# FPGA.net
KiCad netlist of a schematic drawn in Altium Designer
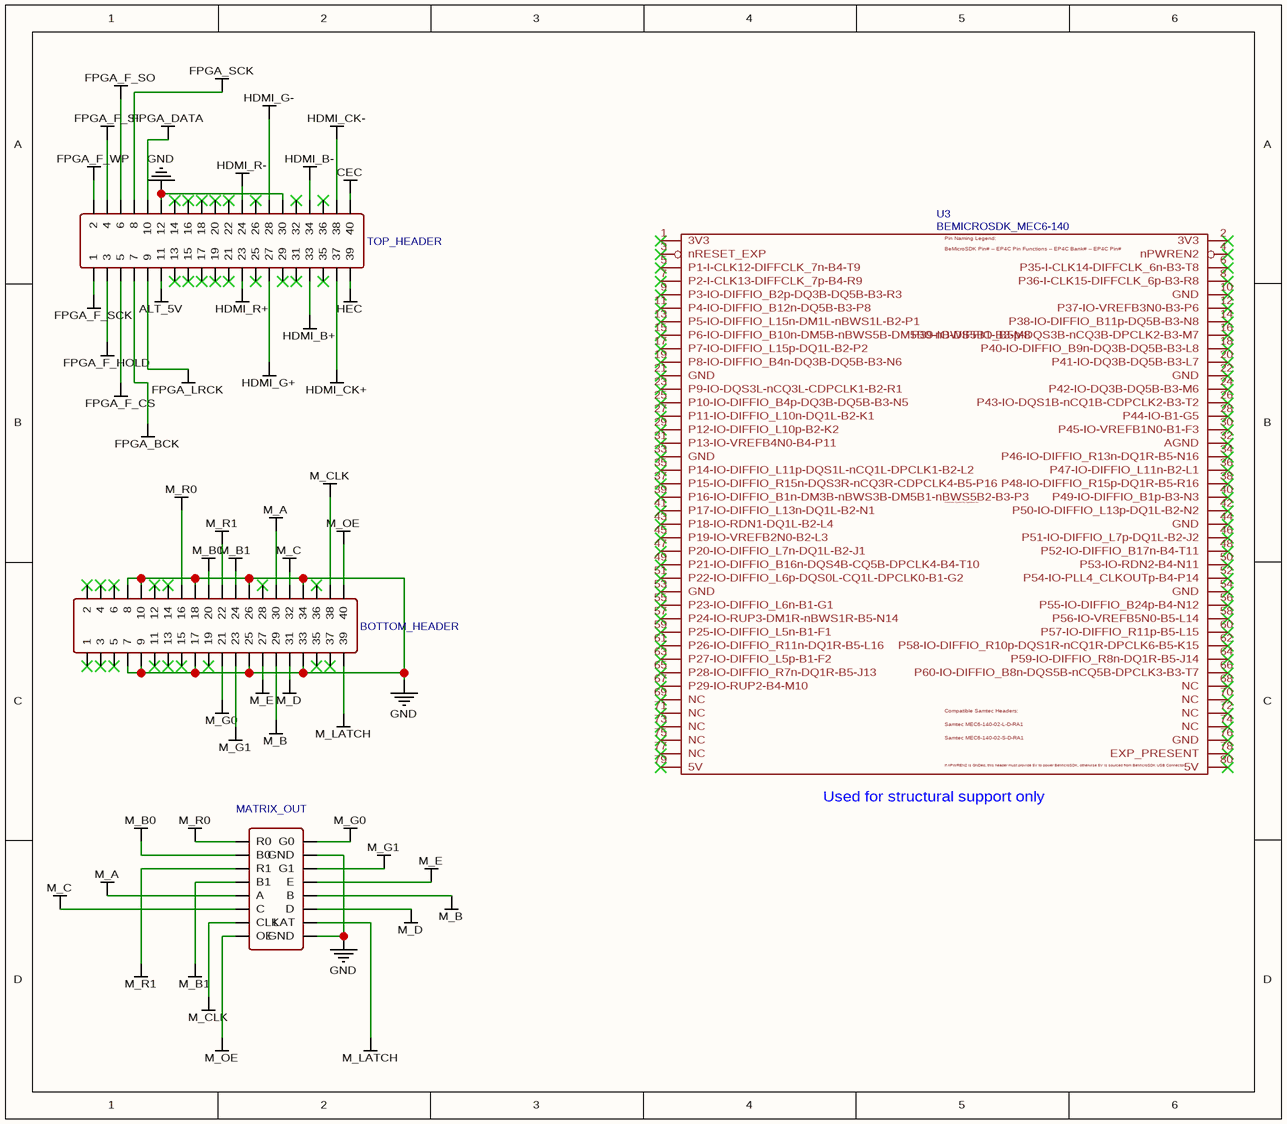
[diagram p0: FPGA.schdoc]

(export (version "E")
  (design (tool "Eeschema 10.0.6"))
  (components
    (comp (ref "BOTTOM_HEADER")
      (value "Header-Male-2.54_2x20")
      (fields (field (name "BOM_SUPPLIER PART") "C50980"))
      (libsource (lib "altium-import") (part "root_1_Header-Male-2.54_2x20_"))
    )
    (comp (ref "MATRIX_OUT")
      (value "MATRIX_OUT")
      (fields
        (field (name "BOM_MANUFACTURER PART") "Double row straight 2*8Headers  Pins 2.54mm")
        (field (name "BOM_SUPPLIER PART") "C68234")
      )
      (libsource (lib "altium-import") (part "root_0_MATRIX_OUT_"))
    )
    (comp (ref "TOP_HEADER")
      (value "Header-Mal0")
      (fields
        (field (name "BOM_MANUFACTURER PART") "Header-Male-2.54_2x20")
        (field (name "BOM_SUPPLIER PART") "C50980")
      )
      (libsource (lib "altium-import") (part "root_1_Header-Mal0_"))
    )
    (comp (ref "U3")
      (value "BEMICROSDK_MEC6-140")
      (fields (field (name "BOM_MANUFACTURER PART") "?"))
      (libsource (lib "altium-import") (part "root_0_BEMICROSDK_MEC6-140_"))
    )
  )
  (nets
    (net (code "1") (name "ALT_5V") (class "Default")
      (node (ref "TOP_HEADER") (pin "11") (pinfunction "11_11") (pintype "passive"))
    )
    (net (code "2") (name "CEC") (class "Default")
      (node (ref "TOP_HEADER") (pin "40") (pinfunction "40_40") (pintype "passive"))
    )
    (net (code "3") (name "FPGA_BCK") (class "Default")
      (node (ref "TOP_HEADER") (pin "7") (pinfunction "7_7") (pintype "passive"))
    )
    (net (code "4") (name "FPGA_DATA") (class "Default")
      (node (ref "TOP_HEADER") (pin "10") (pinfunction "10_10") (pintype "passive"))
    )
    (net (code "5") (name "FPGA_F_CS") (class "Default")
      (node (ref "TOP_HEADER") (pin "5") (pinfunction "5_5") (pintype "passive"))
    )
    (net (code "6") (name "FPGA_F_HOLD") (class "Default")
      (node (ref "TOP_HEADER") (pin "3") (pinfunction "3_3") (pintype "passive"))
    )
    (net (code "7") (name "FPGA_F_SCK") (class "Default")
      (node (ref "TOP_HEADER") (pin "1") (pinfunction "1_1") (pintype "passive"))
    )
    (net (code "8") (name "FPGA_F_SI") (class "Default")
      (node (ref "TOP_HEADER") (pin "4") (pinfunction "4_4") (pintype "passive"))
    )
    (net (code "9") (name "FPGA_F_SO") (class "Default")
      (node (ref "TOP_HEADER") (pin "6") (pinfunction "6_6") (pintype "passive"))
    )
    (net (code "10") (name "FPGA_F_WP") (class "Default")
      (node (ref "TOP_HEADER") (pin "2") (pinfunction "2_2") (pintype "passive"))
    )
    (net (code "11") (name "FPGA_LRCK") (class "Default")
      (node (ref "TOP_HEADER") (pin "9") (pinfunction "9_9") (pintype "passive"))
    )
    (net (code "12") (name "FPGA_SCK") (class "Default")
      (node (ref "TOP_HEADER") (pin "8") (pinfunction "8_8") (pintype "passive"))
    )
    (net (code "13") (name "GND") (class "Default")
      (node (ref "BOTTOM_HEADER") (pin "10") (pinfunction "10_10") (pintype "passive"))
      (node (ref "BOTTOM_HEADER") (pin "17") (pinfunction "17_17") (pintype "passive"))
      (node (ref "BOTTOM_HEADER") (pin "18") (pinfunction "18_18") (pintype "passive"))
      (node (ref "BOTTOM_HEADER") (pin "25") (pinfunction "25_25") (pintype "passive"))
      (node (ref "BOTTOM_HEADER") (pin "26") (pinfunction "26_26") (pintype "passive"))
      (node (ref "BOTTOM_HEADER") (pin "33") (pinfunction "33_33") (pintype "passive"))
      (node (ref "BOTTOM_HEADER") (pin "34") (pinfunction "34_34") (pintype "passive"))
      (node (ref "BOTTOM_HEADER") (pin "7") (pinfunction "7_7") (pintype "passive"))
      (node (ref "BOTTOM_HEADER") (pin "8") (pinfunction "8_8") (pintype "passive"))
      (node (ref "BOTTOM_HEADER") (pin "9") (pinfunction "9_9") (pintype "passive"))
      (node (ref "MATRIX_OUT") (pin "16") (pinfunction "GND_16") (pintype "passive"))
      (node (ref "MATRIX_OUT") (pin "4") (pinfunction "GND_4") (pintype "passive"))
      (node (ref "TOP_HEADER") (pin "12") (pinfunction "12_12") (pintype "passive"))
      (node (ref "TOP_HEADER") (pin "30") (pinfunction "30_30") (pintype "passive"))
    )
    (net (code "14") (name "HDMI_B+") (class "Default")
      (node (ref "TOP_HEADER") (pin "33") (pinfunction "33_33") (pintype "passive"))
    )
    (net (code "15") (name "HDMI_B-") (class "Default")
      (node (ref "TOP_HEADER") (pin "34") (pinfunction "34_34") (pintype "passive"))
    )
    (net (code "16") (name "HDMI_CK+") (class "Default")
      (node (ref "TOP_HEADER") (pin "37") (pinfunction "37_37") (pintype "passive"))
    )
    (net (code "17") (name "HDMI_CK-") (class "Default")
      (node (ref "TOP_HEADER") (pin "38") (pinfunction "38_38") (pintype "passive"))
    )
    (net (code "18") (name "HDMI_G+") (class "Default")
      (node (ref "TOP_HEADER") (pin "27") (pinfunction "27_27") (pintype "passive"))
    )
    (net (code "19") (name "HDMI_G-") (class "Default")
      (node (ref "TOP_HEADER") (pin "28") (pinfunction "28_28") (pintype "passive"))
    )
    (net (code "20") (name "HDMI_R+") (class "Default")
      (node (ref "TOP_HEADER") (pin "23") (pinfunction "23_23") (pintype "passive"))
    )
    (net (code "21") (name "HDMI_R-") (class "Default")
      (node (ref "TOP_HEADER") (pin "24") (pinfunction "24_24") (pintype "passive"))
    )
    (net (code "22") (name "HEC") (class "Default")
      (node (ref "TOP_HEADER") (pin "39") (pinfunction "39_39") (pintype "passive"))
    )
    (net (code "23") (name "M_A") (class "Default")
      (node (ref "BOTTOM_HEADER") (pin "30") (pinfunction "30_30") (pintype "passive"))
      (node (ref "MATRIX_OUT") (pin "9") (pinfunction "A_9") (pintype "passive"))
    )
    (net (code "24") (name "M_B") (class "Default")
      (node (ref "BOTTOM_HEADER") (pin "29") (pinfunction "29_29") (pintype "passive"))
      (node (ref "MATRIX_OUT") (pin "10") (pinfunction "B_10") (pintype "passive"))
    )
    (net (code "25") (name "M_B0") (class "Default")
      (node (ref "BOTTOM_HEADER") (pin "20") (pinfunction "20_20") (pintype "passive"))
      (node (ref "MATRIX_OUT") (pin "3") (pinfunction "B0_3") (pintype "passive"))
    )
    (net (code "26") (name "M_B1") (class "Default")
      (node (ref "BOTTOM_HEADER") (pin "24") (pinfunction "24_24") (pintype "passive"))
      (node (ref "MATRIX_OUT") (pin "7") (pinfunction "B1_7") (pintype "passive"))
    )
    (net (code "27") (name "M_C") (class "Default")
      (node (ref "BOTTOM_HEADER") (pin "32") (pinfunction "32_32") (pintype "passive"))
      (node (ref "MATRIX_OUT") (pin "11") (pinfunction "C_11") (pintype "passive"))
    )
    (net (code "28") (name "M_CLK") (class "Default")
      (node (ref "BOTTOM_HEADER") (pin "38") (pinfunction "38_38") (pintype "passive"))
      (node (ref "MATRIX_OUT") (pin "13") (pinfunction "CLK_13") (pintype "passive"))
    )
    (net (code "29") (name "M_D") (class "Default")
      (node (ref "BOTTOM_HEADER") (pin "31") (pinfunction "31_31") (pintype "passive"))
      (node (ref "MATRIX_OUT") (pin "12") (pinfunction "D_12") (pintype "passive"))
    )
    (net (code "30") (name "M_E") (class "Default")
      (node (ref "BOTTOM_HEADER") (pin "27") (pinfunction "27_27") (pintype "passive"))
      (node (ref "MATRIX_OUT") (pin "8") (pinfunction "E_8") (pintype "passive"))
    )
    (net (code "31") (name "M_G0") (class "Default")
      (node (ref "BOTTOM_HEADER") (pin "21") (pinfunction "21_21") (pintype "passive"))
      (node (ref "MATRIX_OUT") (pin "2") (pinfunction "G0_2") (pintype "passive"))
    )
    (net (code "32") (name "M_G1") (class "Default")
      (node (ref "BOTTOM_HEADER") (pin "23") (pinfunction "23_23") (pintype "passive"))
      (node (ref "MATRIX_OUT") (pin "6") (pinfunction "G1_6") (pintype "passive"))
    )
    (net (code "33") (name "M_LATCH") (class "Default")
      (node (ref "BOTTOM_HEADER") (pin "39") (pinfunction "39_39") (pintype "passive"))
      (node (ref "MATRIX_OUT") (pin "14") (pinfunction "LAT_14") (pintype "passive"))
    )
    (net (code "34") (name "M_OE") (class "Default")
      (node (ref "BOTTOM_HEADER") (pin "40") (pinfunction "40_40") (pintype "passive"))
      (node (ref "MATRIX_OUT") (pin "15") (pinfunction "OE_15") (pintype "passive"))
    )
    (net (code "35") (name "M_R0") (class "Default")
      (node (ref "BOTTOM_HEADER") (pin "16") (pinfunction "16_16") (pintype "passive"))
      (node (ref "MATRIX_OUT") (pin "1") (pinfunction "R0_1") (pintype "passive"))
    )
    (net (code "36") (name "M_R1") (class "Default")
      (node (ref "BOTTOM_HEADER") (pin "22") (pinfunction "22_22") (pintype "passive"))
      (node (ref "MATRIX_OUT") (pin "5") (pinfunction "R1_5") (pintype "passive"))
    )
    (net (code "37") (name "unconnected-(BOTTOM_HEADER-Pad1)") (class "Default")
      (node (ref "BOTTOM_HEADER") (pin "1") (pinfunction "1_1") (pintype "passive+no_connect"))
    )
    (net (code "38") (name "unconnected-(BOTTOM_HEADER-Pad2)") (class "Default")
      (node (ref "BOTTOM_HEADER") (pin "2") (pinfunction "2_2") (pintype "passive+no_connect"))
    )
    (net (code "39") (name "unconnected-(BOTTOM_HEADER-Pad3)") (class "Default")
      (node (ref "BOTTOM_HEADER") (pin "3") (pinfunction "3_3") (pintype "passive+no_connect"))
    )
    (net (code "40") (name "unconnected-(BOTTOM_HEADER-Pad4)") (class "Default")
      (node (ref "BOTTOM_HEADER") (pin "4") (pinfunction "4_4") (pintype "passive+no_connect"))
    )
    (net (code "41") (name "unconnected-(BOTTOM_HEADER-Pad5)") (class "Default")
      (node (ref "BOTTOM_HEADER") (pin "5") (pinfunction "5_5") (pintype "passive+no_connect"))
    )
    (net (code "42") (name "unconnected-(BOTTOM_HEADER-Pad6)") (class "Default")
      (node (ref "BOTTOM_HEADER") (pin "6") (pinfunction "6_6") (pintype "passive+no_connect"))
    )
    (net (code "43") (name "unconnected-(BOTTOM_HEADER-Pad11)") (class "Default")
      (node (ref "BOTTOM_HEADER") (pin "11") (pinfunction "11_11") (pintype "passive+no_connect"))
    )
    (net (code "44") (name "unconnected-(BOTTOM_HEADER-Pad12)") (class "Default")
      (node (ref "BOTTOM_HEADER") (pin "12") (pinfunction "12_12") (pintype "passive+no_connect"))
    )
    (net (code "45") (name "unconnected-(BOTTOM_HEADER-Pad13)") (class "Default")
      (node (ref "BOTTOM_HEADER") (pin "13") (pinfunction "13_13") (pintype "passive+no_connect"))
    )
    (net (code "46") (name "unconnected-(BOTTOM_HEADER-Pad14)") (class "Default")
      (node (ref "BOTTOM_HEADER") (pin "14") (pinfunction "14_14") (pintype "passive+no_connect"))
    )
    (net (code "47") (name "unconnected-(BOTTOM_HEADER-Pad15)") (class "Default")
      (node (ref "BOTTOM_HEADER") (pin "15") (pinfunction "15_15") (pintype "passive+no_connect"))
    )
    (net (code "48") (name "unconnected-(BOTTOM_HEADER-Pad19)") (class "Default")
      (node (ref "BOTTOM_HEADER") (pin "19") (pinfunction "19_19") (pintype "passive+no_connect"))
    )
    (net (code "49") (name "unconnected-(BOTTOM_HEADER-Pad28)") (class "Default")
      (node (ref "BOTTOM_HEADER") (pin "28") (pinfunction "28_28") (pintype "passive+no_connect"))
    )
    (net (code "50") (name "unconnected-(BOTTOM_HEADER-Pad35)") (class "Default")
      (node (ref "BOTTOM_HEADER") (pin "35") (pinfunction "35_35") (pintype "passive+no_connect"))
    )
    (net (code "51") (name "unconnected-(BOTTOM_HEADER-Pad36)") (class "Default")
      (node (ref "BOTTOM_HEADER") (pin "36") (pinfunction "36_36") (pintype "passive+no_connect"))
    )
    (net (code "52") (name "unconnected-(BOTTOM_HEADER-Pad37)") (class "Default")
      (node (ref "BOTTOM_HEADER") (pin "37") (pinfunction "37_37") (pintype "passive+no_connect"))
    )
    (net (code "53") (name "unconnected-(TOP_HEADER-Pad13)") (class "Default")
      (node (ref "TOP_HEADER") (pin "13") (pinfunction "13_13") (pintype "passive+no_connect"))
    )
    (net (code "54") (name "unconnected-(TOP_HEADER-Pad14)") (class "Default")
      (node (ref "TOP_HEADER") (pin "14") (pinfunction "14_14") (pintype "passive+no_connect"))
    )
    (net (code "55") (name "unconnected-(TOP_HEADER-Pad15)") (class "Default")
      (node (ref "TOP_HEADER") (pin "15") (pinfunction "15_15") (pintype "passive+no_connect"))
    )
    (net (code "56") (name "unconnected-(TOP_HEADER-Pad16)") (class "Default")
      (node (ref "TOP_HEADER") (pin "16") (pinfunction "16_16") (pintype "passive+no_connect"))
    )
    (net (code "57") (name "unconnected-(TOP_HEADER-Pad17)") (class "Default")
      (node (ref "TOP_HEADER") (pin "17") (pinfunction "17_17") (pintype "passive+no_connect"))
    )
    (net (code "58") (name "unconnected-(TOP_HEADER-Pad18)") (class "Default")
      (node (ref "TOP_HEADER") (pin "18") (pinfunction "18_18") (pintype "passive+no_connect"))
    )
    (net (code "59") (name "unconnected-(TOP_HEADER-Pad19)") (class "Default")
      (node (ref "TOP_HEADER") (pin "19") (pinfunction "19_19") (pintype "passive+no_connect"))
    )
    (net (code "60") (name "unconnected-(TOP_HEADER-Pad20)") (class "Default")
      (node (ref "TOP_HEADER") (pin "20") (pinfunction "20_20") (pintype "passive+no_connect"))
    )
    (net (code "61") (name "unconnected-(TOP_HEADER-Pad21)") (class "Default")
      (node (ref "TOP_HEADER") (pin "21") (pinfunction "21_21") (pintype "passive+no_connect"))
    )
    (net (code "62") (name "unconnected-(TOP_HEADER-Pad22)") (class "Default")
      (node (ref "TOP_HEADER") (pin "22") (pinfunction "22_22") (pintype "passive+no_connect"))
    )
    (net (code "63") (name "unconnected-(TOP_HEADER-Pad25)") (class "Default")
      (node (ref "TOP_HEADER") (pin "25") (pinfunction "25_25") (pintype "passive+no_connect"))
    )
    (net (code "64") (name "unconnected-(TOP_HEADER-Pad26)") (class "Default")
      (node (ref "TOP_HEADER") (pin "26") (pinfunction "26_26") (pintype "passive+no_connect"))
    )
    (net (code "65") (name "unconnected-(TOP_HEADER-Pad29)") (class "Default")
      (node (ref "TOP_HEADER") (pin "29") (pinfunction "29_29") (pintype "passive+no_connect"))
    )
    (net (code "66") (name "unconnected-(TOP_HEADER-Pad31)") (class "Default")
      (node (ref "TOP_HEADER") (pin "31") (pinfunction "31_31") (pintype "passive+no_connect"))
    )
    (net (code "67") (name "unconnected-(TOP_HEADER-Pad32)") (class "Default")
      (node (ref "TOP_HEADER") (pin "32") (pinfunction "32_32") (pintype "passive+no_connect"))
    )
    (net (code "68") (name "unconnected-(TOP_HEADER-Pad35)") (class "Default")
      (node (ref "TOP_HEADER") (pin "35") (pinfunction "35_35") (pintype "passive+no_connect"))
    )
    (net (code "69") (name "unconnected-(TOP_HEADER-Pad36)") (class "Default")
      (node (ref "TOP_HEADER") (pin "36") (pinfunction "36_36") (pintype "passive+no_connect"))
    )
    (net (code "70") (name "unconnected-(U3-3V3-Pad1)") (class "Default")
      (node (ref "U3") (pin "1") (pinfunction "3V3_1") (pintype "passive+no_connect"))
    )
    (net (code "71") (name "unconnected-(U3-3V3-Pad2)") (class "Default")
      (node (ref "U3") (pin "2") (pinfunction "3V3_2") (pintype "passive+no_connect"))
    )
    (net (code "72") (name "unconnected-(U3-5V-Pad79)") (class "Default")
      (node (ref "U3") (pin "79") (pinfunction "5V_79") (pintype "passive+no_connect"))
    )
    (net (code "73") (name "unconnected-(U3-5V-Pad80)") (class "Default")
      (node (ref "U3") (pin "80") (pinfunction "5V_80") (pintype "passive+no_connect"))
    )
    (net (code "74") (name "unconnected-(U3-AGND-Pad32)") (class "Default")
      (node (ref "U3") (pin "32") (pinfunction "AGND_32") (pintype "passive+no_connect"))
    )
    (net (code "75") (name "unconnected-(U3-EXP_PRESENT-Pad78)") (class "Default")
      (node (ref "U3") (pin "78") (pinfunction "EXP_PRESENT_78") (pintype "passive+no_connect"))
    )
    (net (code "76") (name "unconnected-(U3-GND-Pad10)") (class "Default")
      (node (ref "U3") (pin "10") (pinfunction "GND_10") (pintype "passive+no_connect"))
    )
    (net (code "77") (name "unconnected-(U3-GND-Pad21)") (class "Default")
      (node (ref "U3") (pin "21") (pinfunction "GND_21") (pintype "passive+no_connect"))
    )
    (net (code "78") (name "unconnected-(U3-GND-Pad22)") (class "Default")
      (node (ref "U3") (pin "22") (pinfunction "GND_22") (pintype "passive+no_connect"))
    )
    (net (code "79") (name "unconnected-(U3-GND-Pad33)") (class "Default")
      (node (ref "U3") (pin "33") (pinfunction "GND_33") (pintype "passive+no_connect"))
    )
    (net (code "80") (name "unconnected-(U3-GND-Pad44)") (class "Default")
      (node (ref "U3") (pin "44") (pinfunction "GND_44") (pintype "passive+no_connect"))
    )
    (net (code "81") (name "unconnected-(U3-GND-Pad53)") (class "Default")
      (node (ref "U3") (pin "53") (pinfunction "GND_53") (pintype "passive+no_connect"))
    )
    (net (code "82") (name "unconnected-(U3-GND-Pad54)") (class "Default")
      (node (ref "U3") (pin "54") (pinfunction "GND_54") (pintype "passive+no_connect"))
    )
    (net (code "83") (name "unconnected-(U3-GND-Pad76)") (class "Default")
      (node (ref "U3") (pin "76") (pinfunction "GND_76") (pintype "passive+no_connect"))
    )
    (net (code "84") (name "unconnected-(U3-NC-Pad68)") (class "Default")
      (node (ref "U3") (pin "68") (pinfunction "NC_68") (pintype "passive+no_connect"))
    )
    (net (code "85") (name "unconnected-(U3-NC-Pad69)") (class "Default")
      (node (ref "U3") (pin "69") (pinfunction "NC_69") (pintype "passive+no_connect"))
    )
    (net (code "86") (name "unconnected-(U3-NC-Pad70)") (class "Default")
      (node (ref "U3") (pin "70") (pinfunction "NC_70") (pintype "passive+no_connect"))
    )
    (net (code "87") (name "unconnected-(U3-NC-Pad71)") (class "Default")
      (node (ref "U3") (pin "71") (pinfunction "NC_71") (pintype "passive+no_connect"))
    )
    (net (code "88") (name "unconnected-(U3-NC-Pad72)") (class "Default")
      (node (ref "U3") (pin "72") (pinfunction "NC_72") (pintype "passive+no_connect"))
    )
    (net (code "89") (name "unconnected-(U3-NC-Pad73)") (class "Default")
      (node (ref "U3") (pin "73") (pinfunction "NC_73") (pintype "passive+no_connect"))
    )
    (net (code "90") (name "unconnected-(U3-NC-Pad74)") (class "Default")
      (node (ref "U3") (pin "74") (pinfunction "NC_74") (pintype "passive+no_connect"))
    )
    (net (code "91") (name "unconnected-(U3-NC-Pad75)") (class "Default")
      (node (ref "U3") (pin "75") (pinfunction "NC_75") (pintype "passive+no_connect"))
    )
    (net (code "92") (name "unconnected-(U3-NC-Pad77)") (class "Default")
      (node (ref "U3") (pin "77") (pinfunction "NC_77") (pintype "passive+no_connect"))
    )
    (net (code "93") (name "unconnected-(U3-P1-I-CLK12-DIFFCLK_7n-B4-T9-Pad5)") (class "Default")
      (node (ref "U3") (pin "5") (pinfunction "P1-I-CLK12-DIFFCLK_7n-B4-T9_5") (pintype "passive+no_connect"))
    )
    (net (code "94") (name "unconnected-(U3-P2-I-CLK13-DIFFCLK_7p-B4-R9-Pad7)") (class "Default")
      (node (ref "U3") (pin "7") (pinfunction "P2-I-CLK13-DIFFCLK_7p-B4-R9_7") (pintype "passive+no_connect"))
    )
    (net (code "95") (name "unconnected-(U3-P3-IO-DIFFIO_B2p-DQ3B-DQ5B-B3-R3-Pad9)") (class "Default")
      (node (ref "U3") (pin "9") (pinfunction "P3-IO-DIFFIO_B2p-DQ3B-DQ5B-B3-R3_9") (pintype "passive+no_connect"))
    )
    (net (code "96") (name "unconnected-(U3-P4-IO-DIFFIO_B12n-DQ5B-B3-P8-Pad11)") (class "Default")
      (node (ref "U3") (pin "11") (pinfunction "P4-IO-DIFFIO_B12n-DQ5B-B3-P8_11") (pintype "passive+no_connect"))
    )
    (net (code "97") (name "unconnected-(U3-P5-IO-DIFFIO_L15n-DM1L-nBWS1L-B2-P1-Pad13)") (class "Default")
      (node (ref "U3") (pin "13") (pinfunction "P5-IO-DIFFIO_L15n-DM1L-nBWS1L-B2-P1_13") (pintype "passive+no_connect"))
    )
    (net (code "98") (name "unconnected-(U3-P6-IO-DIFFIO_B10n-DM5B-nBWS5B-DM5B0-nBWS5B1-B3-M8-Pad15)") (class "Default")
      (node (ref "U3") (pin "15") (pinfunction "P6-IO-DIFFIO_B10n-DM5B-nBWS5B-DM5B0-nBWS5B1-B3-M8_15") (pintype "passive+no_connect"))
    )
    (net (code "99") (name "unconnected-(U3-P7-IO-DIFFIO_L15p-DQ1L-B2-P2-Pad17)") (class "Default")
      (node (ref "U3") (pin "17") (pinfunction "P7-IO-DIFFIO_L15p-DQ1L-B2-P2_17") (pintype "passive+no_connect"))
    )
    (net (code "100") (name "unconnected-(U3-P8-IO-DIFFIO_B4n-DQ3B-DQ5B-B3-N6-Pad19)") (class "Default")
      (node (ref "U3") (pin "19") (pinfunction "P8-IO-DIFFIO_B4n-DQ3B-DQ5B-B3-N6_19") (pintype "passive+no_connect"))
    )
    (net (code "101") (name "unconnected-(U3-P9-IO-DQS3L-nCQ3L-CDPCLK1-B2-R1-Pad23)") (class "Default")
      (node (ref "U3") (pin "23") (pinfunction "P9-IO-DQS3L-nCQ3L-CDPCLK1-B2-R1_23") (pintype "passive+no_connect"))
    )
    (net (code "102") (name "unconnected-(U3-P10-IO-DIFFIO_B4p-DQ3B-DQ5B-B3-N5-Pad25)") (class "Default")
      (node (ref "U3") (pin "25") (pinfunction "P10-IO-DIFFIO_B4p-DQ3B-DQ5B-B3-N5_25") (pintype "passive+no_connect"))
    )
    (net (code "103") (name "unconnected-(U3-P11-IO-DIFFIO_L10n-DQ1L-B2-K1-Pad27)") (class "Default")
      (node (ref "U3") (pin "27") (pinfunction "P11-IO-DIFFIO_L10n-DQ1L-B2-K1_27") (pintype "passive+no_connect"))
    )
    (net (code "104") (name "unconnected-(U3-P12-IO-DIFFIO_L10p-B2-K2-Pad29)") (class "Default")
      (node (ref "U3") (pin "29") (pinfunction "P12-IO-DIFFIO_L10p-B2-K2_29") (pintype "passive+no_connect"))
    )
    (net (code "105") (name "unconnected-(U3-P13-IO-VREFB4N0-B4-P11-Pad31)") (class "Default")
      (node (ref "U3") (pin "31") (pinfunction "P13-IO-VREFB4N0-B4-P11_31") (pintype "passive+no_connect"))
    )
    (net (code "106") (name "unconnected-(U3-P14-IO-DIFFIO_L11p-DQS1L-nCQ1L-DPCLK1-B2-L2-Pad35)") (class "Default")
      (node (ref "U3") (pin "35") (pinfunction "P14-IO-DIFFIO_L11p-DQS1L-nCQ1L-DPCLK1-B2-L2_35") (pintype "passive+no_connect"))
    )
    (net (code "107") (name "unconnected-(U3-P15-IO-DIFFIO_R15n-DQS3R-nCQ3R-CDPCLK4-B5-P16-Pad37)") (class "Default")
      (node (ref "U3") (pin "37") (pinfunction "P15-IO-DIFFIO_R15n-DQS3R-nCQ3R-CDPCLK4-B5-P16_37") (pintype "passive+no_connect"))
    )
    (net (code "108") (name "unconnected-(U3-P16-IO-DIFFIO_B1n-DM3B-nBWS3B-DM5B1-nBWS5B2-B3-P3-Pad39)") (class "Default")
      (node (ref "U3") (pin "39") (pinfunction "P16-IO-DIFFIO_B1n-DM3B-nBWS3B-DM5B1-nBWS5B2-B3-P3_39") (pintype "passive+no_connect"))
    )
    (net (code "109") (name "unconnected-(U3-P17-IO-DIFFIO_L13n-DQ1L-B2-N1-Pad41)") (class "Default")
      (node (ref "U3") (pin "41") (pinfunction "P17-IO-DIFFIO_L13n-DQ1L-B2-N1_41") (pintype "passive+no_connect"))
    )
    (net (code "110") (name "unconnected-(U3-P18-IO-RDN1-DQ1L-B2-L4-Pad43)") (class "Default")
      (node (ref "U3") (pin "43") (pinfunction "P18-IO-RDN1-DQ1L-B2-L4_43") (pintype "passive+no_connect"))
    )
    (net (code "111") (name "unconnected-(U3-P19-IO-VREFB2N0-B2-L3-Pad45)") (class "Default")
      (node (ref "U3") (pin "45") (pinfunction "P19-IO-VREFB2N0-B2-L3_45") (pintype "passive+no_connect"))
    )
    (net (code "112") (name "unconnected-(U3-P20-IO-DIFFIO_L7n-DQ1L-B2-J1-Pad47)") (class "Default")
      (node (ref "U3") (pin "47") (pinfunction "P20-IO-DIFFIO_L7n-DQ1L-B2-J1_47") (pintype "passive+no_connect"))
    )
    (net (code "113") (name "unconnected-(U3-P21-IO-DIFFIO_B16n-DQS4B-CQ5B-DPCLK4-B4-T10-Pad49)") (class "Default")
      (node (ref "U3") (pin "49") (pinfunction "P21-IO-DIFFIO_B16n-DQS4B-CQ5B-DPCLK4-B4-T10_49") (pintype "passive+no_connect"))
    )
    (net (code "114") (name "unconnected-(U3-P22-IO-DIFFIO_L6p-DQS0L-CQ1L-DPCLK0-B1-G2-Pad51)") (class "Default")
      (node (ref "U3") (pin "51") (pinfunction "P22-IO-DIFFIO_L6p-DQS0L-CQ1L-DPCLK0-B1-G2_51") (pintype "passive+no_connect"))
    )
    (net (code "115") (name "unconnected-(U3-P23-IO-DIFFIO_L6n-B1-G1-Pad55)") (class "Default")
      (node (ref "U3") (pin "55") (pinfunction "P23-IO-DIFFIO_L6n-B1-G1_55") (pintype "passive+no_connect"))
    )
    (net (code "116") (name "unconnected-(U3-P24-IO-RUP3-DM1R-nBWS1R-B5-N14-Pad57)") (class "Default")
      (node (ref "U3") (pin "57") (pinfunction "P24-IO-RUP3-DM1R-nBWS1R-B5-N14_57") (pintype "passive+no_connect"))
    )
    (net (code "117") (name "unconnected-(U3-P25-IO-DIFFIO_L5n-B1-F1-Pad59)") (class "Default")
      (node (ref "U3") (pin "59") (pinfunction "P25-IO-DIFFIO_L5n-B1-F1_59") (pintype "passive+no_connect"))
    )
    (net (code "118") (name "unconnected-(U3-P26-IO-DIFFIO_R11n-DQ1R-B5-L16-Pad61)") (class "Default")
      (node (ref "U3") (pin "61") (pinfunction "P26-IO-DIFFIO_R11n-DQ1R-B5-L16_61") (pintype "passive+no_connect"))
    )
    (net (code "119") (name "unconnected-(U3-P27-IO-DIFFIO_L5p-B1-F2-Pad63)") (class "Default")
      (node (ref "U3") (pin "63") (pinfunction "P27-IO-DIFFIO_L5p-B1-F2_63") (pintype "passive+no_connect"))
    )
    (net (code "120") (name "unconnected-(U3-P28-IO-DIFFIO_R7n-DQ1R-B5-J13-Pad65)") (class "Default")
      (node (ref "U3") (pin "65") (pinfunction "P28-IO-DIFFIO_R7n-DQ1R-B5-J13_65") (pintype "passive+no_connect"))
    )
    (net (code "121") (name "unconnected-(U3-P29-IO-RUP2-B4-M10-Pad67)") (class "Default")
      (node (ref "U3") (pin "67") (pinfunction "P29-IO-RUP2-B4-M10_67") (pintype "passive+no_connect"))
    )
    (net (code "122") (name "unconnected-(U3-P35-I-CLK14-DIFFCLK_6n-B3-T8-Pad6)") (class "Default")
      (node (ref "U3") (pin "6") (pinfunction "P35-I-CLK14-DIFFCLK_6n-B3-T8_6") (pintype "passive+no_connect"))
    )
    (net (code "123") (name "unconnected-(U3-P36-I-CLK15-DIFFCLK_6p-B3-R8-Pad8)") (class "Default")
      (node (ref "U3") (pin "8") (pinfunction "P36-I-CLK15-DIFFCLK_6p-B3-R8_8") (pintype "passive+no_connect"))
    )
    (net (code "124") (name "unconnected-(U3-P37-IO-VREFB3N0-B3-P6-Pad12)") (class "Default")
      (node (ref "U3") (pin "12") (pinfunction "P37-IO-VREFB3N0-B3-P6_12") (pintype "passive+no_connect"))
    )
    (net (code "125") (name "unconnected-(U3-P38-IO-DIFFIO_B11p-DQ5B-B3-N8-Pad14)") (class "Default")
      (node (ref "U3") (pin "14") (pinfunction "P38-IO-DIFFIO_B11p-DQ5B-B3-N8_14") (pintype "passive+no_connect"))
    )
    (net (code "126") (name "unconnected-(U3-P39-IO-DIFFIO_B5p-DQS3B-nCQ3B-DPCLK2-B3-M7-Pad16)") (class "Default")
      (node (ref "U3") (pin "16") (pinfunction "P39-IO-DIFFIO_B5p-DQS3B-nCQ3B-DPCLK2-B3-M7_16") (pintype "passive+no_connect"))
    )
    (net (code "127") (name "unconnected-(U3-P40-IO-DIFFIO_B9n-DQ3B-DQ5B-B3-L8-Pad18)") (class "Default")
      (node (ref "U3") (pin "18") (pinfunction "P40-IO-DIFFIO_B9n-DQ3B-DQ5B-B3-L8_18") (pintype "passive+no_connect"))
    )
    (net (code "128") (name "unconnected-(U3-P41-IO-DQ3B-DQ5B-B3-L7-Pad20)") (class "Default")
      (node (ref "U3") (pin "20") (pinfunction "P41-IO-DQ3B-DQ5B-B3-L7_20") (pintype "passive+no_connect"))
    )
    (net (code "129") (name "unconnected-(U3-P42-IO-DQ3B-DQ5B-B3-M6-Pad24)") (class "Default")
      (node (ref "U3") (pin "24") (pinfunction "P42-IO-DQ3B-DQ5B-B3-M6_24") (pintype "passive+no_connect"))
    )
    (net (code "130") (name "unconnected-(U3-P43-IO-DQS1B-nCQ1B-CDPCLK2-B3-T2-Pad26)") (class "Default")
      (node (ref "U3") (pin "26") (pinfunction "P43-IO-DQS1B-nCQ1B-CDPCLK2-B3-T2_26") (pintype "passive+no_connect"))
    )
    (net (code "131") (name "unconnected-(U3-P44-IO-B1-G5-Pad28)") (class "Default")
      (node (ref "U3") (pin "28") (pinfunction "P44-IO-B1-G5_28") (pintype "passive+no_connect"))
    )
    (net (code "132") (name "unconnected-(U3-P45-IO-VREFB1N0-B1-F3-Pad30)") (class "Default")
      (node (ref "U3") (pin "30") (pinfunction "P45-IO-VREFB1N0-B1-F3_30") (pintype "passive+no_connect"))
    )
    (net (code "133") (name "unconnected-(U3-P46-IO-DIFFIO_R13n-DQ1R-B5-N16-Pad34)") (class "Default")
      (node (ref "U3") (pin "34") (pinfunction "P46-IO-DIFFIO_R13n-DQ1R-B5-N16_34") (pintype "passive+no_connect"))
    )
    (net (code "134") (name "unconnected-(U3-P47-IO-DIFFIO_L11n-B2-L1-Pad36)") (class "Default")
      (node (ref "U3") (pin "36") (pinfunction "P47-IO-DIFFIO_L11n-B2-L1_36") (pintype "passive+no_connect"))
    )
    (net (code "135") (name "unconnected-(U3-P48-IO-DIFFIO_R15p-DQ1R-B5-R16-Pad38)") (class "Default")
      (node (ref "U3") (pin "38") (pinfunction "P48-IO-DIFFIO_R15p-DQ1R-B5-R16_38") (pintype "passive+no_connect"))
    )
    (net (code "136") (name "unconnected-(U3-P49-IO-DIFFIO_B1p-B3-N3-Pad40)") (class "Default")
      (node (ref "U3") (pin "40") (pinfunction "P49-IO-DIFFIO_B1p-B3-N3_40") (pintype "passive+no_connect"))
    )
    (net (code "137") (name "unconnected-(U3-P50-IO-DIFFIO_L13p-DQ1L-B2-N2-Pad42)") (class "Default")
      (node (ref "U3") (pin "42") (pinfunction "P50-IO-DIFFIO_L13p-DQ1L-B2-N2_42") (pintype "passive+no_connect"))
    )
    (net (code "138") (name "unconnected-(U3-P51-IO-DIFFIO_L7p-DQ1L-B2-J2-Pad46)") (class "Default")
      (node (ref "U3") (pin "46") (pinfunction "P51-IO-DIFFIO_L7p-DQ1L-B2-J2_46") (pintype "passive+no_connect"))
    )
    (net (code "139") (name "unconnected-(U3-P52-IO-DIFFIO_B17n-B4-T11-Pad48)") (class "Default")
      (node (ref "U3") (pin "48") (pinfunction "P52-IO-DIFFIO_B17n-B4-T11_48") (pintype "passive+no_connect"))
    )
    (net (code "140") (name "unconnected-(U3-P53-IO-RDN2-B4-N11-Pad50)") (class "Default")
      (node (ref "U3") (pin "50") (pinfunction "P53-IO-RDN2-B4-N11_50") (pintype "passive+no_connect"))
    )
    (net (code "141") (name "unconnected-(U3-P54-IO-PLL4_CLKOUTp-B4-P14-Pad52)") (class "Default")
      (node (ref "U3") (pin "52") (pinfunction "P54-IO-PLL4_CLKOUTp-B4-P14_52") (pintype "passive+no_connect"))
    )
    (net (code "142") (name "unconnected-(U3-P55-IO-DIFFIO_B24p-B4-N12-Pad56)") (class "Default")
      (node (ref "U3") (pin "56") (pinfunction "P55-IO-DIFFIO_B24p-B4-N12_56") (pintype "passive+no_connect"))
    )
    (net (code "143") (name "unconnected-(U3-P56-IO-VREFB5N0-B5-L14-Pad58)") (class "Default")
      (node (ref "U3") (pin "58") (pinfunction "P56-IO-VREFB5N0-B5-L14_58") (pintype "passive+no_connect"))
    )
    (net (code "144") (name "unconnected-(U3-P57-IO-DIFFIO_R11p-B5-L15-Pad60)") (class "Default")
      (node (ref "U3") (pin "60") (pinfunction "P57-IO-DIFFIO_R11p-B5-L15_60") (pintype "passive+no_connect"))
    )
    (net (code "145") (name "unconnected-(U3-P58-IO-DIFFIO_R10p-DQS1R-nCQ1R-DPCLK6-B5-K15-Pad62)") (class "Default")
      (node (ref "U3") (pin "62") (pinfunction "P58-IO-DIFFIO_R10p-DQS1R-nCQ1R-DPCLK6-B5-K15_62") (pintype "passive+no_connect"))
    )
    (net (code "146") (name "unconnected-(U3-P59-IO-DIFFIO_R8n-DQ1R-B5-J14-Pad64)") (class "Default")
      (node (ref "U3") (pin "64") (pinfunction "P59-IO-DIFFIO_R8n-DQ1R-B5-J14_64") (pintype "passive+no_connect"))
    )
    (net (code "147") (name "unconnected-(U3-P60-IO-DIFFIO_B8n-DQS5B-nCQ5B-DPCLK3-B3-T7-Pad66)") (class "Default")
      (node (ref "U3") (pin "66") (pinfunction "P60-IO-DIFFIO_B8n-DQS5B-nCQ5B-DPCLK3-B3-T7_66") (pintype "passive+no_connect"))
    )
    (net (code "148") (name "unconnected-(U3-nPWREN2-Pad4)") (class "Default")
      (node (ref "U3") (pin "4") (pinfunction "nPWREN2_4") (pintype "passive+no_connect"))
    )
    (net (code "149") (name "unconnected-(U3-nRESET_EXP-Pad3)") (class "Default")
      (node (ref "U3") (pin "3") (pinfunction "nRESET_EXP_3") (pintype "passive+no_connect"))
    )
  )
)
